# CLIPPER_SCHEMATIC.net
KiCad netlist of a schematic drawn in EasyEDA
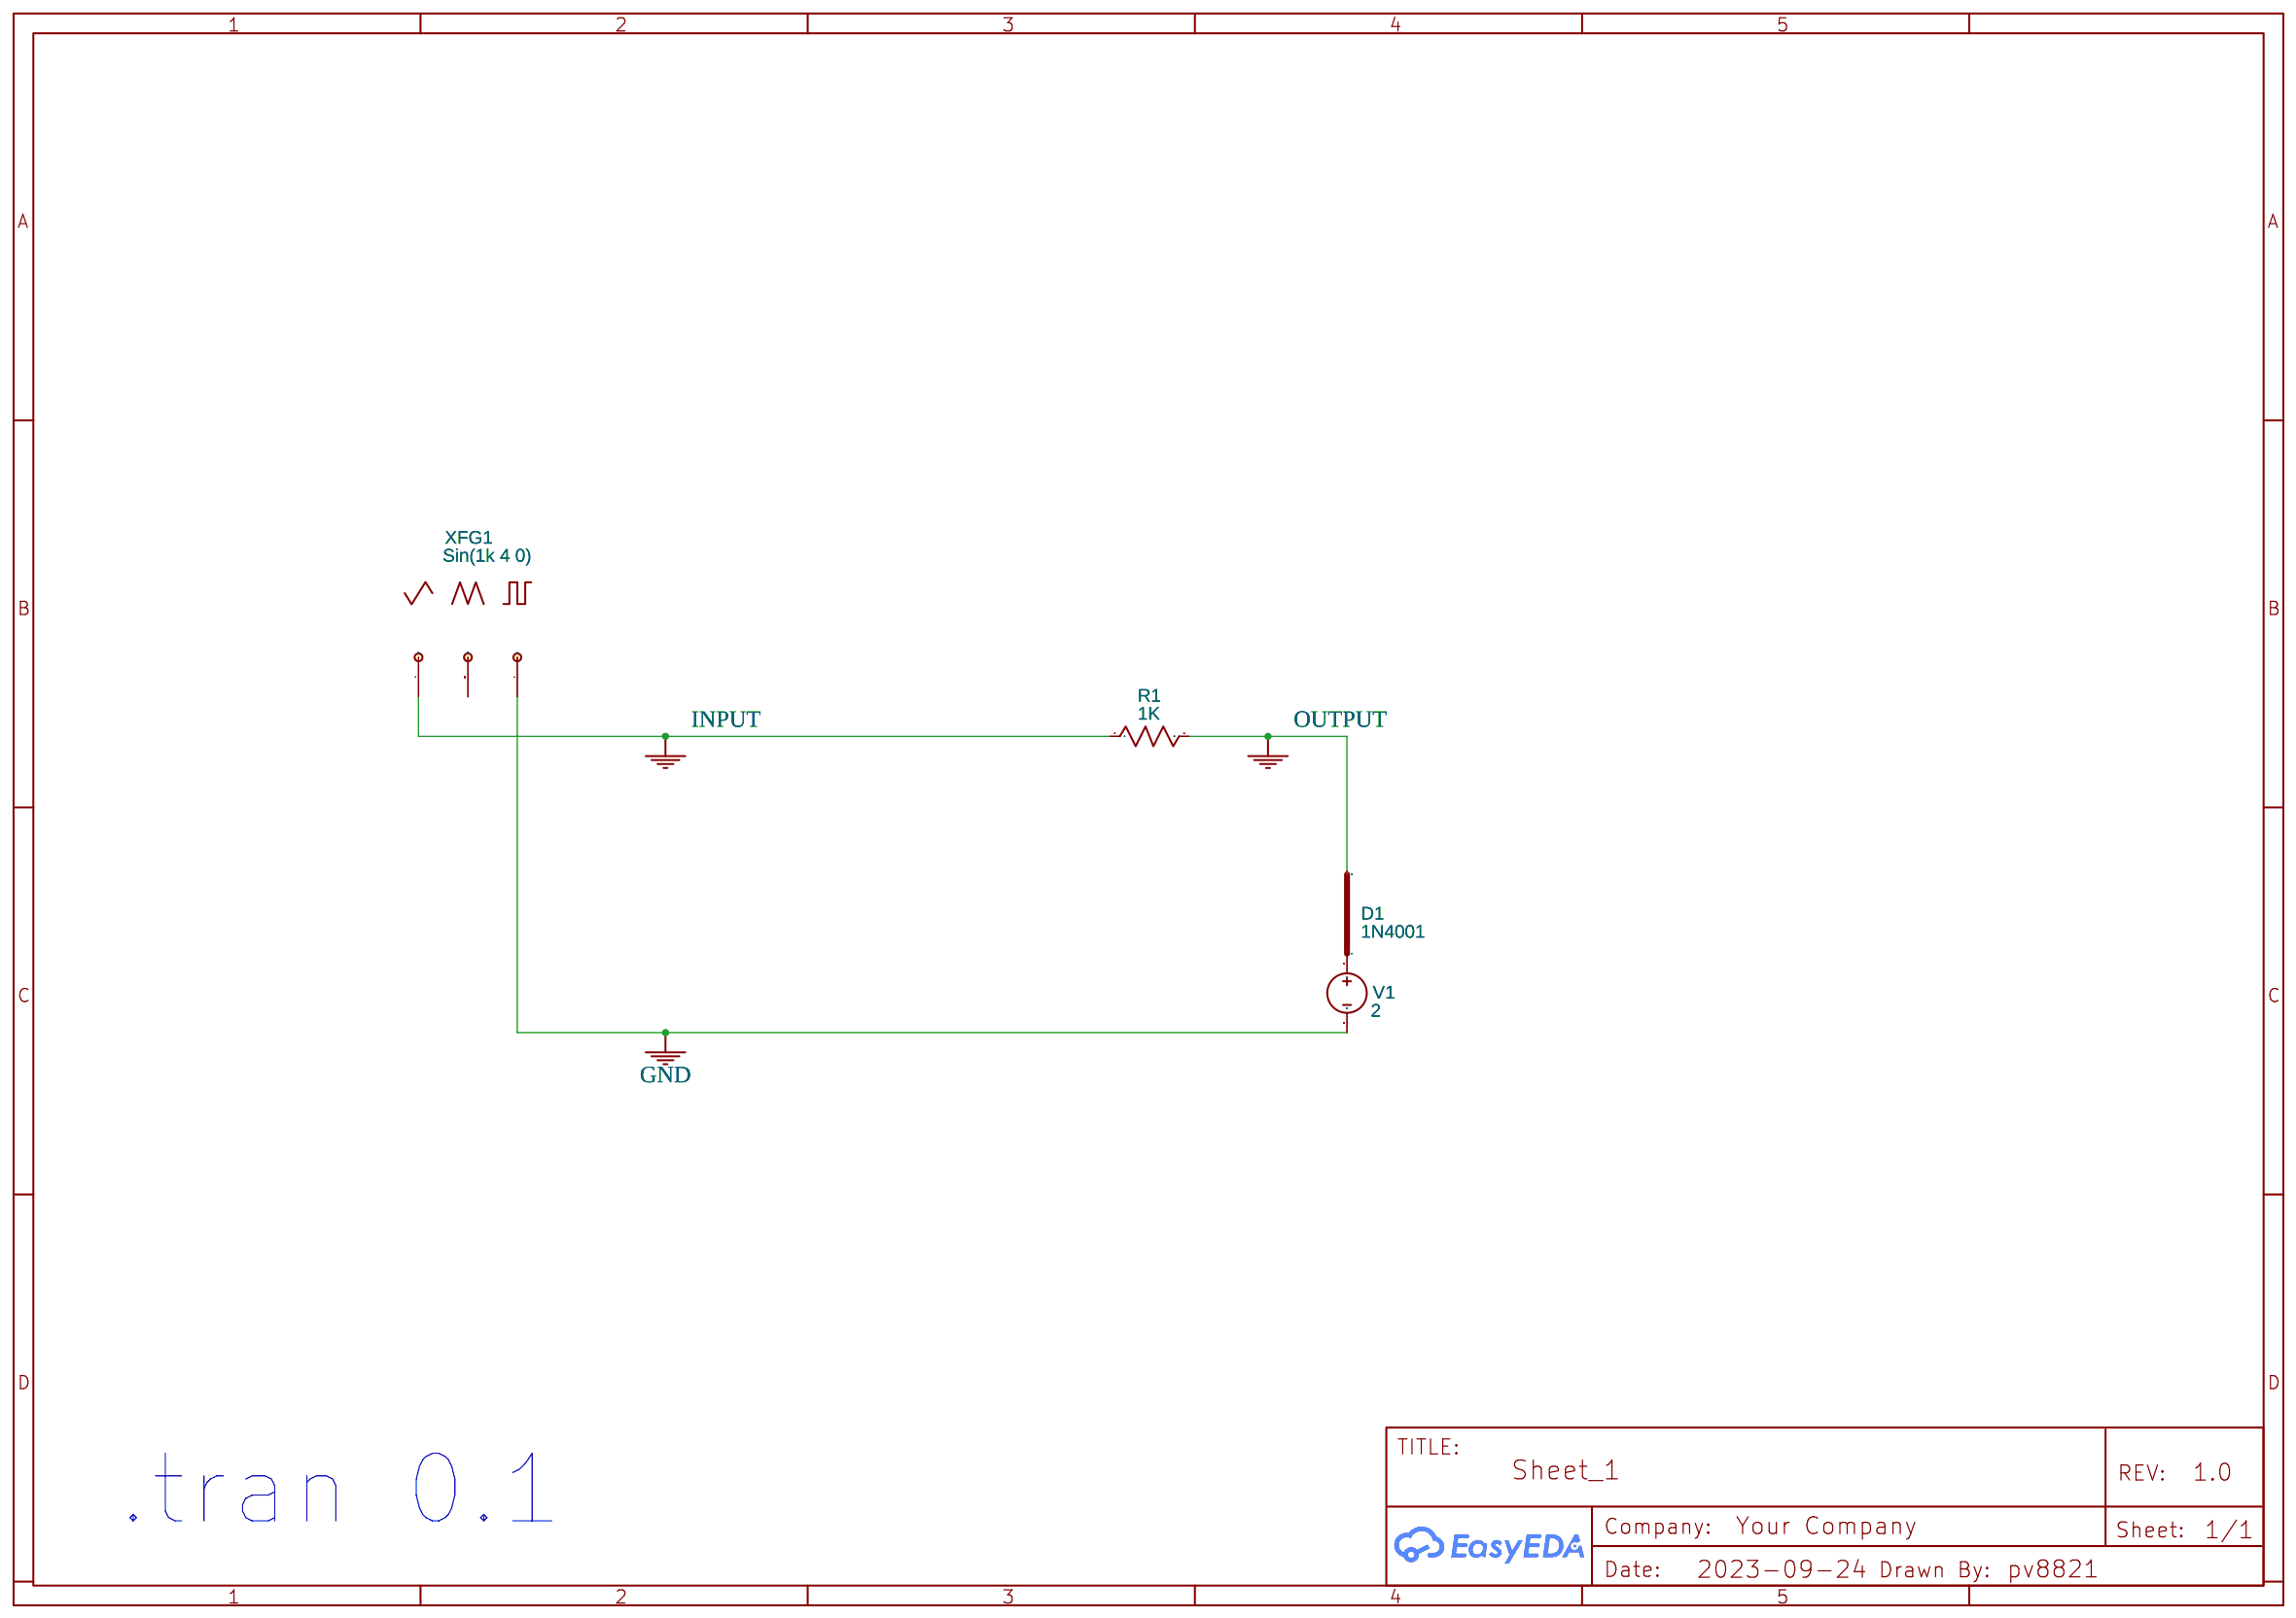
[diagram p0: schematic sheet]

(export (version "E")
  (design (tool "Eeschema 10.0.6"))
  (components
    (comp (ref "D1") (value "1N4001") (libsource (lib "") (part "1N4001")))
    (comp (ref "R1") (value "1K") (libsource (lib "") (part "Resistor_US")))
    (comp (ref "V1") (value "2") (libsource (lib "") (part "VDC")))
    (comp (ref "XFG1") (value "Sin(1k 4 0)") (libsource (lib "") (part "FUNCTIONGENERATOR")))
  )
  (nets
    (net (code "1") (name "GND") (class "Default")
      (node (ref "V1") (pin "2") (pinfunction "2_2") (pintype "unspecified"))
      (node (ref "XFG1") (pin "-") (pinfunction "-_-") (pintype "unspecified"))
    )
    (net (code "2") (name "INPUT") (class "Default")
      (node (ref "R1") (pin "1") (pinfunction "1_1") (pintype "unspecified"))
      (node (ref "XFG1") (pin "+") (pinfunction "+_+") (pintype "unspecified"))
    )
    (net (code "3") (name "Net-(D1-Pad1)") (class "Default")
      (node (ref "D1") (pin "1") (pinfunction "1_1") (pintype "unspecified"))
      (node (ref "V1") (pin "1") (pinfunction "1_1") (pintype "unspecified"))
    )
    (net (code "4") (name "OUTPUT") (class "Default")
      (node (ref "D1") (pin "2") (pinfunction "2_2") (pintype "unspecified"))
      (node (ref "R1") (pin "2") (pinfunction "2_2") (pintype "unspecified"))
    )
    (net (code "5") (name "unconnected-(XFG1-PadCOM)") (class "Default")
      (node (ref "XFG1") (pin "COM") (pinfunction "COM_COM") (pintype "unspecified"))
    )
  )
)
